# Powerboard.net
KiCad netlist of a schematic drawn in EAGLE
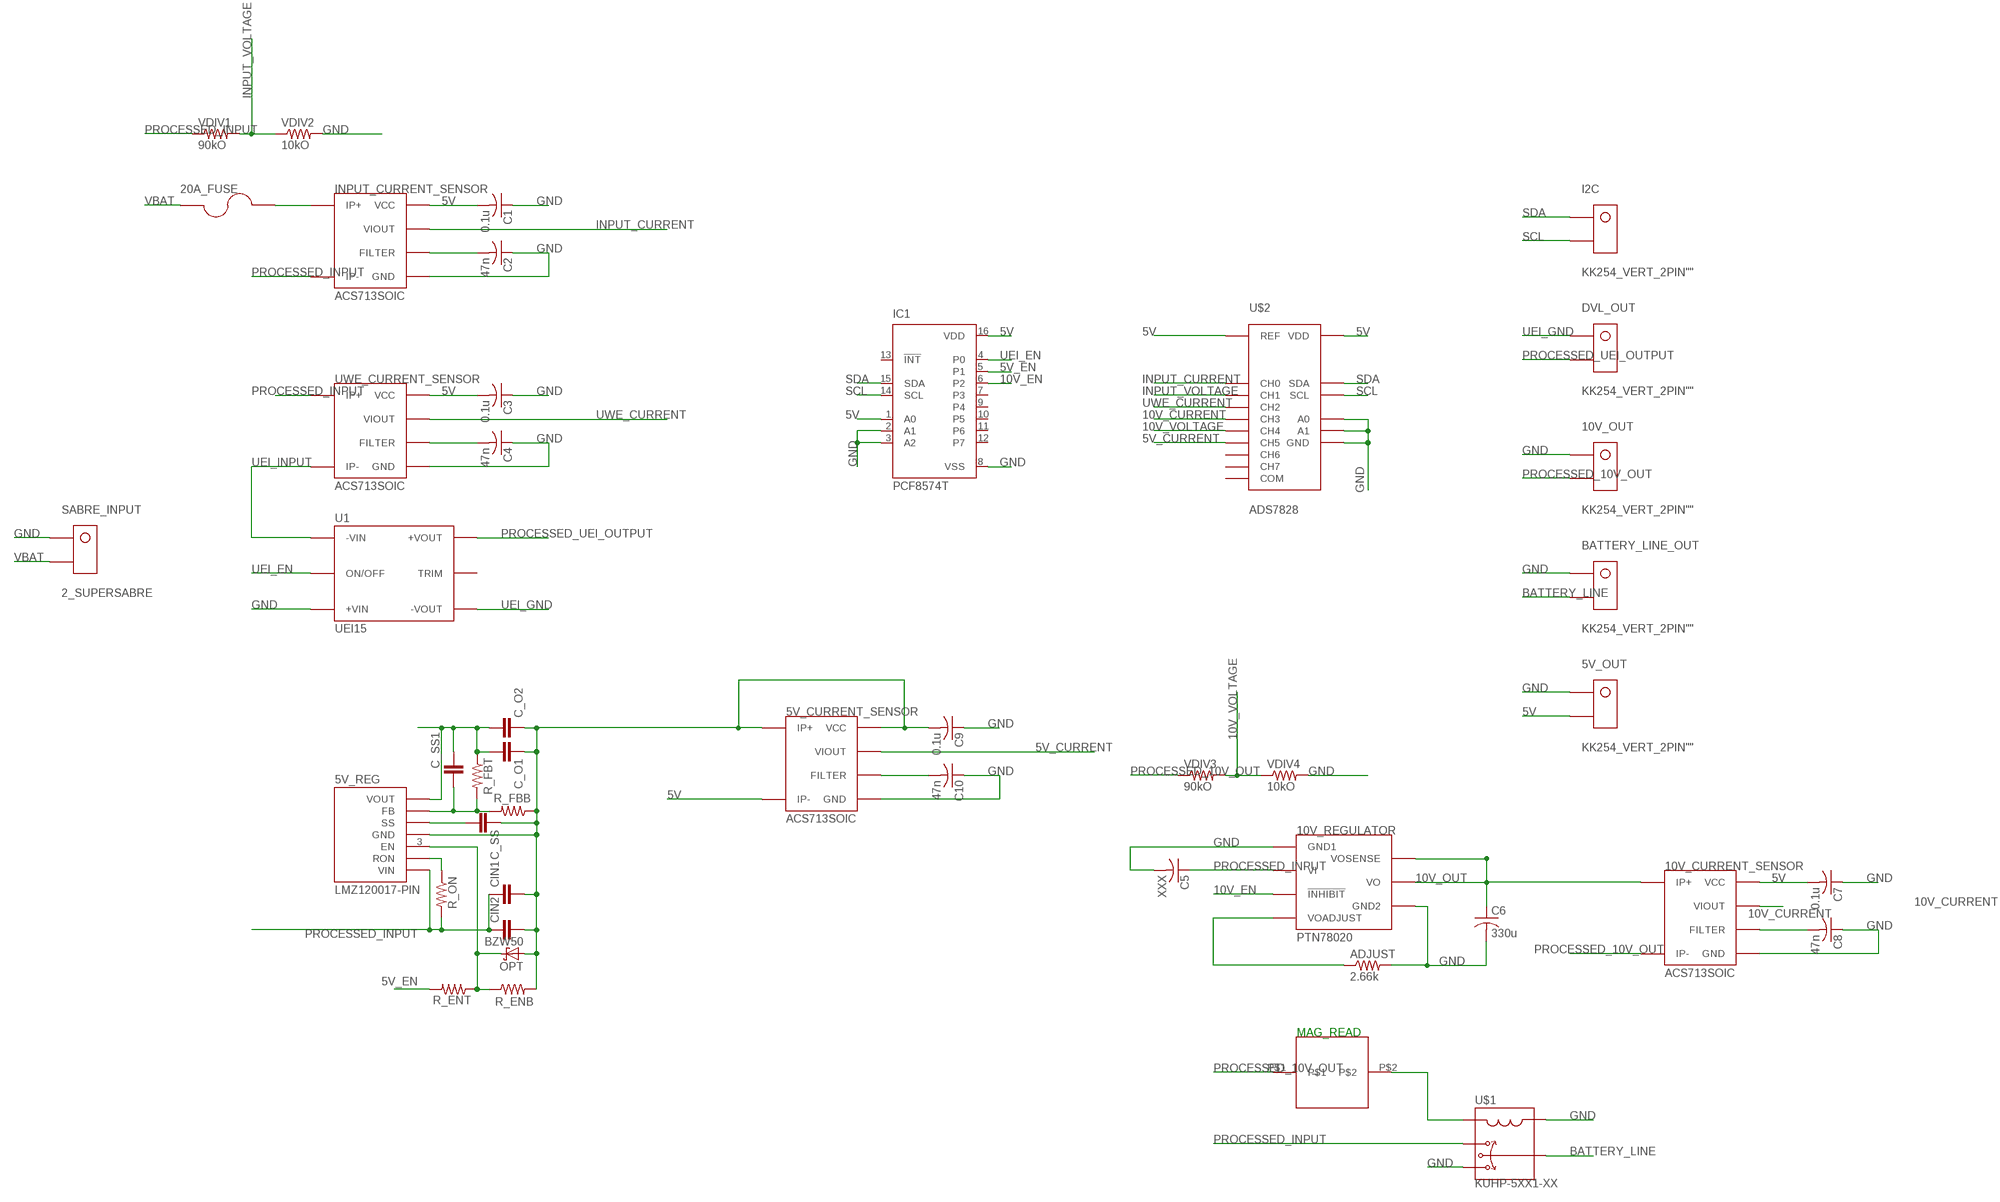
[diagram p0: schematic, sheet 1]

(export (version "E")
  (design (tool "Eeschema 10.0.6"))
  (components
    (comp (ref "5V_CURRENT_SENSOR")
      (value "ACS713SOIC")
      (footprint "eagle-import:ACS713-SOIC")
      (libsource (lib "eagle-import") (part "ACS713SOIC"))
    )
    (comp (ref "5V_OUT")
      (value "KK254_VERT_2PIN\"\"")
      (footprint "eagle-import:KK254_VERT_2PIN")
      (libsource (lib "eagle-import") (part "KK254_VERT_2PIN{dblquote}{dblquote}"))
    )
    (comp (ref "5V_REG")
      (value "LMZ120017-PIN")
      (footprint "eagle-import:LMZ12001")
      (libsource (lib "eagle-import") (part "LMZ120017-PIN"))
    )
    (comp (ref "10V_CURRENT_SENSOR")
      (value "ACS713SOIC")
      (footprint "eagle-import:ACS713-SOIC")
      (libsource (lib "eagle-import") (part "ACS713SOIC"))
    )
    (comp (ref "10V_OUT")
      (value "KK254_VERT_2PIN\"\"")
      (footprint "eagle-import:KK254_VERT_2PIN")
      (libsource (lib "eagle-import") (part "KK254_VERT_2PIN{dblquote}{dblquote}"))
    )
    (comp (ref "10V_REGULATOR")
      (value "PTN78020")
      (footprint "eagle-import:PTN")
      (libsource (lib "eagle-import") (part "PTN78020"))
    )
    (comp (ref "20A_FUSE")
      (value "BOWED-1.25\"-FUSECLIPS")
      (footprint "eagle-import:1.25__FUSECLIPS")
      (libsource (lib "eagle-import") (part "BOWED-1.25{dblquote}-FUSECLIPS"))
    )
    (comp (ref "ADJUST")
      (value "2.66k")
      (footprint "eagle-import:R0805")
      (libsource (lib "eagle-import") (part "R-US_R0805"))
    )
    (comp (ref "BATTERY_LINE_OUT")
      (value "KK254_VERT_2PIN\"\"")
      (footprint "eagle-import:KK254_VERT_2PIN")
      (libsource (lib "eagle-import") (part "KK254_VERT_2PIN{dblquote}{dblquote}"))
    )
    (comp (ref "C1")
      (value "0.1u")
      (footprint "eagle-import:C0805")
      (libsource (lib "eagle-import") (part "C-USC0805"))
    )
    (comp (ref "C2")
      (value "47n")
      (footprint "eagle-import:C0805")
      (libsource (lib "eagle-import") (part "C-USC0805"))
    )
    (comp (ref "C3")
      (value "0.1u")
      (footprint "eagle-import:C0805")
      (libsource (lib "eagle-import") (part "C-USC0805"))
    )
    (comp (ref "C4")
      (value "47n")
      (footprint "eagle-import:C0805")
      (libsource (lib "eagle-import") (part "C-USC0805"))
    )
    (comp (ref "C5")
      (value "XXX")
      (footprint "eagle-import:C0805")
      (libsource (lib "eagle-import") (part "C-USC0805"))
    )
    (comp (ref "C6")
      (value "330u")
      (footprint "eagle-import:C0805")
      (libsource (lib "eagle-import") (part "C-USC0805"))
    )
    (comp (ref "C7")
      (value "0.1u")
      (footprint "eagle-import:C0805")
      (libsource (lib "eagle-import") (part "C-USC0805"))
    )
    (comp (ref "C8")
      (value "47n")
      (footprint "eagle-import:C0805")
      (libsource (lib "eagle-import") (part "C-USC0805"))
    )
    (comp (ref "C9")
      (value "0.1u")
      (footprint "eagle-import:C0805")
      (libsource (lib "eagle-import") (part "C-USC0805"))
    )
    (comp (ref "C10")
      (value "47n")
      (footprint "eagle-import:C0805")
      (libsource (lib "eagle-import") (part "C-USC0805"))
    )
    (comp (ref "CIN1")
      (value "C5/3.5")
      (footprint "eagle-import:C5B3.5")
      (libsource (lib "eagle-import") (part "C5/3.5"))
    )
    (comp (ref "CIN2")
      (value "C5/3.5")
      (footprint "eagle-import:C5B3.5")
      (libsource (lib "eagle-import") (part "C5/3.5"))
    )
    (comp (ref "C_O1")
      (value "C5/3.5")
      (footprint "eagle-import:C5B3.5")
      (libsource (lib "eagle-import") (part "C5/3.5"))
    )
    (comp (ref "C_O2")
      (value "C5/3.5")
      (footprint "eagle-import:C5B3.5")
      (libsource (lib "eagle-import") (part "C5/3.5"))
    )
    (comp (ref "C_SS")
      (value "C5/3.5")
      (footprint "eagle-import:C5B3.5")
      (libsource (lib "eagle-import") (part "C5/3.5"))
    )
    (comp (ref "C_SS1")
      (value "C5/3.5")
      (footprint "eagle-import:C5B3.5")
      (libsource (lib "eagle-import") (part "C5/3.5"))
    )
    (comp (ref "DVL_OUT")
      (value "KK254_VERT_2PIN\"\"")
      (footprint "eagle-import:KK254_VERT_2PIN")
      (libsource (lib "eagle-import") (part "KK254_VERT_2PIN{dblquote}{dblquote}"))
    )
    (comp (ref "I2C")
      (value "KK254_VERT_2PIN\"\"")
      (footprint "eagle-import:KK254_VERT_2PIN")
      (libsource (lib "eagle-import") (part "KK254_VERT_2PIN{dblquote}{dblquote}"))
    )
    (comp (ref "IC1")
      (value "PCF8574T")
      (footprint "eagle-import:SO16W")
      (fields (field (name "MPN") "PCF8574T/3,512"))
      (libsource (lib "eagle-import") (part "PCF8574T"))
    )
    (comp (ref "INPUT_CURRENT_SENSOR")
      (value "ACS713SOIC")
      (footprint "eagle-import:ACS713-SOIC")
      (libsource (lib "eagle-import") (part "ACS713SOIC"))
    )
    (comp (ref "MAGREAD")
      (value "HE151TR-ND")
      (footprint "eagle-import:HE151TR-ND")
      (libsource (lib "eagle-import") (part "HE151TR-ND"))
    )
    (comp (ref "OPT")
      (value "BZW50")
      (footprint "eagle-import:AG")
      (libsource (lib "eagle-import") (part "BZW50"))
    )
    (comp (ref "R_ENB")
      (value "R-US_R0805")
      (footprint "eagle-import:R0805")
      (libsource (lib "eagle-import") (part "R-US_R0805"))
    )
    (comp (ref "R_ENT")
      (value "R-US_R0805")
      (footprint "eagle-import:R0805")
      (libsource (lib "eagle-import") (part "R-US_R0805"))
    )
    (comp (ref "R_FBB")
      (value "R-US_R0805")
      (footprint "eagle-import:R0805")
      (libsource (lib "eagle-import") (part "R-US_R0805"))
    )
    (comp (ref "R_FBT")
      (value "R-US_R0805")
      (footprint "eagle-import:R0805")
      (libsource (lib "eagle-import") (part "R-US_R0805"))
    )
    (comp (ref "R_ON")
      (value "R-US_R0805")
      (footprint "eagle-import:R0805")
      (libsource (lib "eagle-import") (part "R-US_R0805"))
    )
    (comp (ref "SABRE_INPUT")
      (value "2_SUPERSABRE")
      (footprint "eagle-import:SUPERSABRE_2CIRCUIT")
      (libsource (lib "eagle-import") (part "2_SUPERSABRE"))
    )
    (comp (ref "U$1")
      (value "KUHP-5XX1-XX")
      (footprint "eagle-import:KUHP_6.35MM-QUICK-CONNECT")
      (libsource (lib "eagle-import") (part "KUHP-5XX1-XX"))
    )
    (comp (ref "U$2")
      (value "ADS7828")
      (footprint "eagle-import:TSSOP16")
      (libsource (lib "eagle-import") (part "ADS7828"))
    )
    (comp (ref "U1")
      (value "UEI15")
      (footprint "eagle-import:UEI15")
      (libsource (lib "eagle-import") (part "UEI15"))
    )
    (comp (ref "UWE_CURRENT_SENSOR")
      (value "ACS713SOIC")
      (footprint "eagle-import:ACS713-SOIC")
      (libsource (lib "eagle-import") (part "ACS713SOIC"))
    )
    (comp (ref "VDIV1")
      (value "90kO")
      (footprint "eagle-import:R0805")
      (libsource (lib "eagle-import") (part "R-US_R0805"))
    )
    (comp (ref "VDIV2")
      (value "10kO")
      (footprint "eagle-import:R0805")
      (libsource (lib "eagle-import") (part "R-US_R0805"))
    )
    (comp (ref "VDIV3")
      (value "90kO")
      (footprint "eagle-import:R0805")
      (libsource (lib "eagle-import") (part "R-US_R0805"))
    )
    (comp (ref "VDIV4")
      (value "10kO")
      (footprint "eagle-import:R0805")
      (libsource (lib "eagle-import") (part "R-US_R0805"))
    )
  )
  (nets
    (net (code "1") (name "/5V") (class "Default")
      (node (ref "10V_CURRENT_SENSOR") (pin "P$8") (pinfunction "VCC_P$8") (pintype "bidirectional"))
      (node (ref "5V_CURRENT_SENSOR") (pin "P$3") (pinfunction "IP-_P$3") (pintype "bidirectional"))
      (node (ref "5V_CURRENT_SENSOR") (pin "P$4") (pinfunction "IP-_P$4") (pintype "bidirectional"))
      (node (ref "5V_OUT") (pin "P$2") (pinfunction "P$2_P$2") (pintype "bidirectional"))
      (node (ref "C1") (pin "2") (pinfunction "2_2") (pintype "passive"))
      (node (ref "C3") (pin "2") (pinfunction "2_2") (pintype "passive"))
      (node (ref "C7") (pin "2") (pinfunction "2_2") (pintype "passive"))
      (node (ref "IC1") (pin "1") (pinfunction "A0_1") (pintype "input"))
      (node (ref "IC1") (pin "16") (pinfunction "VDD_16") (pintype "power_in"))
      (node (ref "INPUT_CURRENT_SENSOR") (pin "P$8") (pinfunction "VCC_P$8") (pintype "bidirectional"))
      (node (ref "U$2") (pin "10") (pinfunction "REF_10") (pintype "bidirectional"))
      (node (ref "U$2") (pin "16") (pinfunction "VDD_16") (pintype "bidirectional"))
      (node (ref "UWE_CURRENT_SENSOR") (pin "P$8") (pinfunction "VCC_P$8") (pintype "bidirectional"))
    )
    (net (code "2") (name "/5V_CURRENT") (class "Default")
      (node (ref "5V_CURRENT_SENSOR") (pin "P$7") (pinfunction "VIOUT_P$7") (pintype "bidirectional"))
      (node (ref "U$2") (pin "6") (pinfunction "CH5_6") (pintype "bidirectional"))
    )
    (net (code "3") (name "/5V_EN") (class "Default")
      (node (ref "IC1") (pin "5") (pinfunction "P1_5") (pintype "bidirectional"))
      (node (ref "R_ENT") (pin "2") (pinfunction "2_2") (pintype "passive"))
    )
    (net (code "4") (name "/10V_CURRENT") (class "Default")
      (node (ref "10V_CURRENT_SENSOR") (pin "P$7") (pinfunction "VIOUT_P$7") (pintype "bidirectional"))
      (node (ref "U$2") (pin "4") (pinfunction "CH3_4") (pintype "bidirectional"))
    )
    (net (code "5") (name "/10V_EN") (class "Default")
      (node (ref "10V_REGULATOR") (pin "INHIBIT") (pinfunction "~{INHIBIT}_INHIBIT") (pintype "bidirectional"))
      (node (ref "IC1") (pin "6") (pinfunction "P2_6") (pintype "bidirectional"))
    )
    (net (code "6") (name "/10V_OUT") (class "Default")
      (node (ref "10V_CURRENT_SENSOR") (pin "P$1") (pinfunction "IP+_P$1") (pintype "bidirectional"))
      (node (ref "10V_CURRENT_SENSOR") (pin "P$2") (pinfunction "IP+_P$2") (pintype "bidirectional"))
      (node (ref "10V_REGULATOR") (pin "SENSE") (pinfunction "VOSENSE_SENSE") (pintype "bidirectional"))
      (node (ref "10V_REGULATOR") (pin "VOUT") (pinfunction "VO_VOUT") (pintype "bidirectional"))
      (node (ref "C6") (pin "1") (pinfunction "1_1") (pintype "passive"))
    )
    (net (code "7") (name "/10V_VOLTAGE") (class "Default")
      (node (ref "U$2") (pin "5") (pinfunction "CH4_5") (pintype "bidirectional"))
      (node (ref "VDIV3") (pin "2") (pinfunction "2_2") (pintype "passive"))
      (node (ref "VDIV4") (pin "1") (pinfunction "1_1") (pintype "passive"))
    )
    (net (code "8") (name "/BATTERY_LINE") (class "Default")
      (node (ref "BATTERY_LINE_OUT") (pin "P$2") (pinfunction "P$2_P$2") (pintype "bidirectional"))
      (node (ref "U$1") (pin "7A") (pinfunction "7_7A") (pintype "bidirectional"))
      (node (ref "U$1") (pin "7B") (pinfunction "7_7B") (pintype "bidirectional"))
    )
    (net (code "9") (name "/GND") (class "Default")
      (node (ref "10V_CURRENT_SENSOR") (pin "P$5") (pinfunction "GND_P$5") (pintype "bidirectional"))
      (node (ref "10V_OUT") (pin "P$1") (pinfunction "P$1_P$1") (pintype "bidirectional"))
      (node (ref "10V_REGULATOR") (pin "GND1") (pinfunction "GND1_GND1") (pintype "bidirectional"))
      (node (ref "10V_REGULATOR") (pin "GND2") (pinfunction "GND2_GND2") (pintype "bidirectional"))
      (node (ref "5V_CURRENT_SENSOR") (pin "P$5") (pinfunction "GND_P$5") (pintype "bidirectional"))
      (node (ref "5V_OUT") (pin "P$1") (pinfunction "P$1_P$1") (pintype "bidirectional"))
      (node (ref "ADJUST") (pin "2") (pinfunction "2_2") (pintype "passive"))
      (node (ref "BATTERY_LINE_OUT") (pin "P$1") (pinfunction "P$1_P$1") (pintype "bidirectional"))
      (node (ref "C1") (pin "1") (pinfunction "1_1") (pintype "passive"))
      (node (ref "C10") (pin "1") (pinfunction "1_1") (pintype "passive"))
      (node (ref "C2") (pin "1") (pinfunction "1_1") (pintype "passive"))
      (node (ref "C3") (pin "1") (pinfunction "1_1") (pintype "passive"))
      (node (ref "C4") (pin "1") (pinfunction "1_1") (pintype "passive"))
      (node (ref "C5") (pin "2") (pinfunction "2_2") (pintype "passive"))
      (node (ref "C6") (pin "2") (pinfunction "2_2") (pintype "passive"))
      (node (ref "C7") (pin "1") (pinfunction "1_1") (pintype "passive"))
      (node (ref "C8") (pin "1") (pinfunction "1_1") (pintype "passive"))
      (node (ref "C9") (pin "1") (pinfunction "1_1") (pintype "passive"))
      (node (ref "IC1") (pin "2") (pinfunction "A1_2") (pintype "input"))
      (node (ref "IC1") (pin "3") (pinfunction "A2_3") (pintype "input"))
      (node (ref "IC1") (pin "8") (pinfunction "VSS_8") (pintype "power_in"))
      (node (ref "INPUT_CURRENT_SENSOR") (pin "P$5") (pinfunction "GND_P$5") (pintype "bidirectional"))
      (node (ref "SABRE_INPUT") (pin "P$1") (pinfunction "P$1_P$1") (pintype "bidirectional"))
      (node (ref "U$1") (pin "5A") (pinfunction "5_5A") (pintype "bidirectional"))
      (node (ref "U$1") (pin "5B") (pinfunction "5_5B") (pintype "bidirectional"))
      (node (ref "U$1") (pin "AA") (pinfunction "A_AA") (pintype "bidirectional"))
      (node (ref "U$1") (pin "AB") (pinfunction "A_AB") (pintype "bidirectional"))
      (node (ref "U$2") (pin "12") (pinfunction "A0_12") (pintype "bidirectional"))
      (node (ref "U$2") (pin "13") (pinfunction "A1_13") (pintype "bidirectional"))
      (node (ref "U$2") (pin "9") (pinfunction "GND_9") (pintype "bidirectional"))
      (node (ref "U1") (pin "P$6") (pinfunction "+VIN_P$6") (pintype "power_in"))
      (node (ref "UWE_CURRENT_SENSOR") (pin "P$5") (pinfunction "GND_P$5") (pintype "bidirectional"))
      (node (ref "VDIV2") (pin "2") (pinfunction "2_2") (pintype "passive"))
      (node (ref "VDIV4") (pin "2") (pinfunction "2_2") (pintype "passive"))
    )
    (net (code "10") (name "/INPUT_CURRENT") (class "Default")
      (node (ref "INPUT_CURRENT_SENSOR") (pin "P$7") (pinfunction "VIOUT_P$7") (pintype "bidirectional"))
      (node (ref "U$2") (pin "1") (pinfunction "CH0_1") (pintype "bidirectional"))
    )
    (net (code "11") (name "/INPUT_VOLTAGE") (class "Default")
      (node (ref "U$2") (pin "2") (pinfunction "CH1_2") (pintype "bidirectional"))
      (node (ref "VDIV1") (pin "2") (pinfunction "2_2") (pintype "passive"))
      (node (ref "VDIV2") (pin "1") (pinfunction "1_1") (pintype "passive"))
    )
    (net (code "12") (name "/PROCESSED_10V_OUT") (class "Default")
      (node (ref "10V_CURRENT_SENSOR") (pin "P$3") (pinfunction "IP-_P$3") (pintype "bidirectional"))
      (node (ref "10V_CURRENT_SENSOR") (pin "P$4") (pinfunction "IP-_P$4") (pintype "bidirectional"))
      (node (ref "10V_OUT") (pin "P$2") (pinfunction "P$2_P$2") (pintype "bidirectional"))
      (node (ref "MAGREAD") (pin "P$1") (pinfunction "P$1_P$1") (pintype "bidirectional"))
      (node (ref "VDIV3") (pin "1") (pinfunction "1_1") (pintype "passive"))
    )
    (net (code "13") (name "/PROCESSED_INPUT") (class "Default")
      (node (ref "10V_REGULATOR") (pin "VIN") (pinfunction "VI_VIN") (pintype "bidirectional"))
      (node (ref "5V_CURRENT_SENSOR") (pin "P$1") (pinfunction "IP+_P$1") (pintype "bidirectional"))
      (node (ref "5V_CURRENT_SENSOR") (pin "P$2") (pinfunction "IP+_P$2") (pintype "bidirectional"))
      (node (ref "5V_CURRENT_SENSOR") (pin "P$8") (pinfunction "VCC_P$8") (pintype "bidirectional"))
      (node (ref "5V_REG") (pin "1") (pinfunction "VIN_1") (pintype "power_in"))
      (node (ref "5V_REG") (pin "4") (pinfunction "GND_4") (pintype "power_in"))
      (node (ref "C5") (pin "1") (pinfunction "1_1") (pintype "passive"))
      (node (ref "C9") (pin "2") (pinfunction "2_2") (pintype "passive"))
      (node (ref "CIN1") (pin "1") (pinfunction "1_1") (pintype "passive"))
      (node (ref "CIN1") (pin "2") (pinfunction "2_2") (pintype "passive"))
      (node (ref "CIN2") (pin "1") (pinfunction "1_1") (pintype "passive"))
      (node (ref "CIN2") (pin "2") (pinfunction "2_2") (pintype "passive"))
      (node (ref "C_O1") (pin "1") (pinfunction "1_1") (pintype "passive"))
      (node (ref "C_O2") (pin "1") (pinfunction "1_1") (pintype "passive"))
      (node (ref "C_SS") (pin "1") (pinfunction "1_1") (pintype "passive"))
      (node (ref "INPUT_CURRENT_SENSOR") (pin "P$3") (pinfunction "IP-_P$3") (pintype "bidirectional"))
      (node (ref "INPUT_CURRENT_SENSOR") (pin "P$4") (pinfunction "IP-_P$4") (pintype "bidirectional"))
      (node (ref "OPT") (pin "A") (pinfunction "A_A") (pintype "passive"))
      (node (ref "R_ENB") (pin "2") (pinfunction "2_2") (pintype "passive"))
      (node (ref "R_FBB") (pin "1") (pinfunction "1_1") (pintype "passive"))
      (node (ref "R_ON") (pin "2") (pinfunction "2_2") (pintype "passive"))
      (node (ref "U$1") (pin "2A") (pinfunction "2_2A") (pintype "bidirectional"))
      (node (ref "U$1") (pin "2B") (pinfunction "2_2B") (pintype "bidirectional"))
      (node (ref "UWE_CURRENT_SENSOR") (pin "P$1") (pinfunction "IP+_P$1") (pintype "bidirectional"))
      (node (ref "UWE_CURRENT_SENSOR") (pin "P$2") (pinfunction "IP+_P$2") (pintype "bidirectional"))
      (node (ref "VDIV1") (pin "1") (pinfunction "1_1") (pintype "passive"))
    )
    (net (code "14") (name "/PROCESSED_UEI_OUTPUT") (class "Default")
      (node (ref "DVL_OUT") (pin "P$2") (pinfunction "P$2_P$2") (pintype "bidirectional"))
      (node (ref "U1") (pin "P$1") (pinfunction "+VOUT_P$1") (pintype "power_in"))
    )
    (net (code "15") (name "/SCL") (class "Default")
      (node (ref "I2C") (pin "P$2") (pinfunction "P$2_P$2") (pintype "bidirectional"))
      (node (ref "IC1") (pin "14") (pinfunction "SCL_14") (pintype "input"))
      (node (ref "U$2") (pin "14") (pinfunction "SCL_14") (pintype "bidirectional"))
    )
    (net (code "16") (name "/SDA") (class "Default")
      (node (ref "I2C") (pin "P$1") (pinfunction "P$1_P$1") (pintype "bidirectional"))
      (node (ref "IC1") (pin "15") (pinfunction "SDA_15") (pintype "bidirectional"))
      (node (ref "U$2") (pin "15") (pinfunction "SDA_15") (pintype "bidirectional"))
    )
    (net (code "17") (name "/UEI_EN") (class "Default")
      (node (ref "IC1") (pin "4") (pinfunction "P0_4") (pintype "bidirectional"))
      (node (ref "U1") (pin "P$4") (pinfunction "ON/OFF_P$4") (pintype "bidirectional"))
    )
    (net (code "18") (name "/UEI_GND") (class "Default")
      (node (ref "DVL_OUT") (pin "P$1") (pinfunction "P$1_P$1") (pintype "bidirectional"))
      (node (ref "U1") (pin "P$3") (pinfunction "-VOUT_P$3") (pintype "power_in"))
    )
    (net (code "19") (name "/UEI_INPUT") (class "Default")
      (node (ref "U1") (pin "P$5") (pinfunction "-VIN_P$5") (pintype "power_in"))
      (node (ref "UWE_CURRENT_SENSOR") (pin "P$3") (pinfunction "IP-_P$3") (pintype "bidirectional"))
      (node (ref "UWE_CURRENT_SENSOR") (pin "P$4") (pinfunction "IP-_P$4") (pintype "bidirectional"))
    )
    (net (code "20") (name "/UWE_CURRENT") (class "Default")
      (node (ref "U$2") (pin "3") (pinfunction "CH2_3") (pintype "bidirectional"))
      (node (ref "UWE_CURRENT_SENSOR") (pin "P$7") (pinfunction "VIOUT_P$7") (pintype "bidirectional"))
    )
    (net (code "21") (name "/VBAT") (class "Default")
      (node (ref "20A_FUSE") (pin "P$1") (pinfunction "P$1_P$1") (pintype "bidirectional"))
      (node (ref "20A_FUSE") (pin "P$2") (pinfunction "P$1_P$2") (pintype "bidirectional"))
      (node (ref "SABRE_INPUT") (pin "P$2") (pinfunction "P$2_P$2") (pintype "bidirectional"))
    )
    (net (code "22") (name "Net-(5V_CURRENT_SENSOR-FILTER)") (class "Default")
      (node (ref "5V_CURRENT_SENSOR") (pin "P$6") (pinfunction "FILTER_P$6") (pintype "bidirectional"))
      (node (ref "C10") (pin "2") (pinfunction "2_2") (pintype "passive"))
    )
    (net (code "23") (name "Net-(5V_REG-EN)") (class "Default")
      (node (ref "5V_REG") (pin "3") (pinfunction "EN_3") (pintype "bidirectional"))
      (node (ref "OPT") (pin "C") (pinfunction "C_C") (pintype "passive"))
      (node (ref "R_ENB") (pin "1") (pinfunction "1_1") (pintype "passive"))
      (node (ref "R_ENT") (pin "1") (pinfunction "1_1") (pintype "passive"))
    )
    (net (code "24") (name "Net-(5V_REG-FB)") (class "Default")
      (node (ref "5V_REG") (pin "6") (pinfunction "FB_6") (pintype "bidirectional"))
      (node (ref "C_SS1") (pin "2") (pinfunction "2_2") (pintype "passive"))
      (node (ref "R_FBB") (pin "2") (pinfunction "2_2") (pintype "passive"))
      (node (ref "R_FBT") (pin "2") (pinfunction "2_2") (pintype "passive"))
    )
    (net (code "25") (name "Net-(5V_REG-RON)") (class "Default")
      (node (ref "5V_REG") (pin "2") (pinfunction "RON_2") (pintype "bidirectional"))
      (node (ref "R_ON") (pin "1") (pinfunction "1_1") (pintype "passive"))
    )
    (net (code "26") (name "Net-(5V_REG-SS)") (class "Default")
      (node (ref "5V_REG") (pin "5") (pinfunction "SS_5") (pintype "bidirectional"))
      (node (ref "C_SS") (pin "2") (pinfunction "2_2") (pintype "passive"))
    )
    (net (code "27") (name "Net-(5V_REG-VOUT)") (class "Default")
      (node (ref "5V_REG") (pin "7") (pinfunction "VOUT_7") (pintype "power_in"))
      (node (ref "C_O1") (pin "2") (pinfunction "2_2") (pintype "passive"))
      (node (ref "C_O2") (pin "2") (pinfunction "2_2") (pintype "passive"))
      (node (ref "C_SS1") (pin "1") (pinfunction "1_1") (pintype "passive"))
      (node (ref "R_FBT") (pin "1") (pinfunction "1_1") (pintype "passive"))
    )
    (net (code "28") (name "Net-(10V_CURRENT_SENSOR-FILTER)") (class "Default")
      (node (ref "10V_CURRENT_SENSOR") (pin "P$6") (pinfunction "FILTER_P$6") (pintype "bidirectional"))
      (node (ref "C8") (pin "2") (pinfunction "2_2") (pintype "passive"))
    )
    (net (code "29") (name "Net-(10V_REGULATOR-VOADJUST)") (class "Default")
      (node (ref "10V_REGULATOR") (pin "ADJUST") (pinfunction "VOADJUST_ADJUST") (pintype "bidirectional"))
      (node (ref "ADJUST") (pin "1") (pinfunction "1_1") (pintype "passive"))
    )
    (net (code "30") (name "Net-(20A_FUSE-P$2-PadP$3)") (class "Default")
      (node (ref "20A_FUSE") (pin "P$3") (pinfunction "P$2_P$3") (pintype "bidirectional"))
      (node (ref "20A_FUSE") (pin "P$4") (pinfunction "P$2_P$4") (pintype "bidirectional"))
      (node (ref "INPUT_CURRENT_SENSOR") (pin "P$1") (pinfunction "IP+_P$1") (pintype "bidirectional"))
      (node (ref "INPUT_CURRENT_SENSOR") (pin "P$2") (pinfunction "IP+_P$2") (pintype "bidirectional"))
    )
    (net (code "31") (name "Net-(INPUT_CURRENT_SENSOR-FILTER)") (class "Default")
      (node (ref "C2") (pin "2") (pinfunction "2_2") (pintype "passive"))
      (node (ref "INPUT_CURRENT_SENSOR") (pin "P$6") (pinfunction "FILTER_P$6") (pintype "bidirectional"))
    )
    (net (code "32") (name "Net-(MAGREAD-PadP$2)") (class "Default")
      (node (ref "MAGREAD") (pin "P$2") (pinfunction "P$2_P$2") (pintype "bidirectional"))
      (node (ref "U$1") (pin "BA") (pinfunction "B_BA") (pintype "bidirectional"))
      (node (ref "U$1") (pin "BB") (pinfunction "B_BB") (pintype "bidirectional"))
    )
    (net (code "33") (name "Net-(UWE_CURRENT_SENSOR-FILTER)") (class "Default")
      (node (ref "C4") (pin "2") (pinfunction "2_2") (pintype "passive"))
      (node (ref "UWE_CURRENT_SENSOR") (pin "P$6") (pinfunction "FILTER_P$6") (pintype "bidirectional"))
    )
    (net (code "34") (name "unconnected-(IC1-P3-Pad7)") (class "Default")
      (node (ref "IC1") (pin "7") (pinfunction "P3_7") (pintype "bidirectional"))
    )
    (net (code "35") (name "unconnected-(IC1-P4-Pad9)") (class "Default")
      (node (ref "IC1") (pin "9") (pinfunction "P4_9") (pintype "bidirectional"))
    )
    (net (code "36") (name "unconnected-(IC1-P5-Pad10)") (class "Default")
      (node (ref "IC1") (pin "10") (pinfunction "P5_10") (pintype "bidirectional"))
    )
    (net (code "37") (name "unconnected-(IC1-P6-Pad11)") (class "Default")
      (node (ref "IC1") (pin "11") (pinfunction "P6_11") (pintype "bidirectional"))
    )
    (net (code "38") (name "unconnected-(IC1-P7-Pad12)") (class "Default")
      (node (ref "IC1") (pin "12") (pinfunction "P7_12") (pintype "bidirectional"))
    )
    (net (code "39") (name "unconnected-(IC1-~{INT}-Pad13)") (class "Default")
      (node (ref "IC1") (pin "13") (pinfunction "~{INT}_13") (pintype "output"))
    )
    (net (code "40") (name "unconnected-(U$2-CH6-Pad7)") (class "Default")
      (node (ref "U$2") (pin "7") (pinfunction "CH6_7") (pintype "bidirectional"))
    )
    (net (code "41") (name "unconnected-(U$2-CH7-Pad8)") (class "Default")
      (node (ref "U$2") (pin "8") (pinfunction "CH7_8") (pintype "bidirectional"))
    )
    (net (code "42") (name "unconnected-(U$2-COM-Pad11)") (class "Default")
      (node (ref "U$2") (pin "11") (pinfunction "COM_11") (pintype "bidirectional"))
    )
    (net (code "43") (name "unconnected-(U1-TRIM-PadP$2)") (class "Default")
      (node (ref "U1") (pin "P$2") (pinfunction "TRIM_P$2") (pintype "bidirectional"))
    )
  )
)
